# joint_board_boosterpack_load_cell.net
KiCad netlist of a schematic drawn in Altium Designer
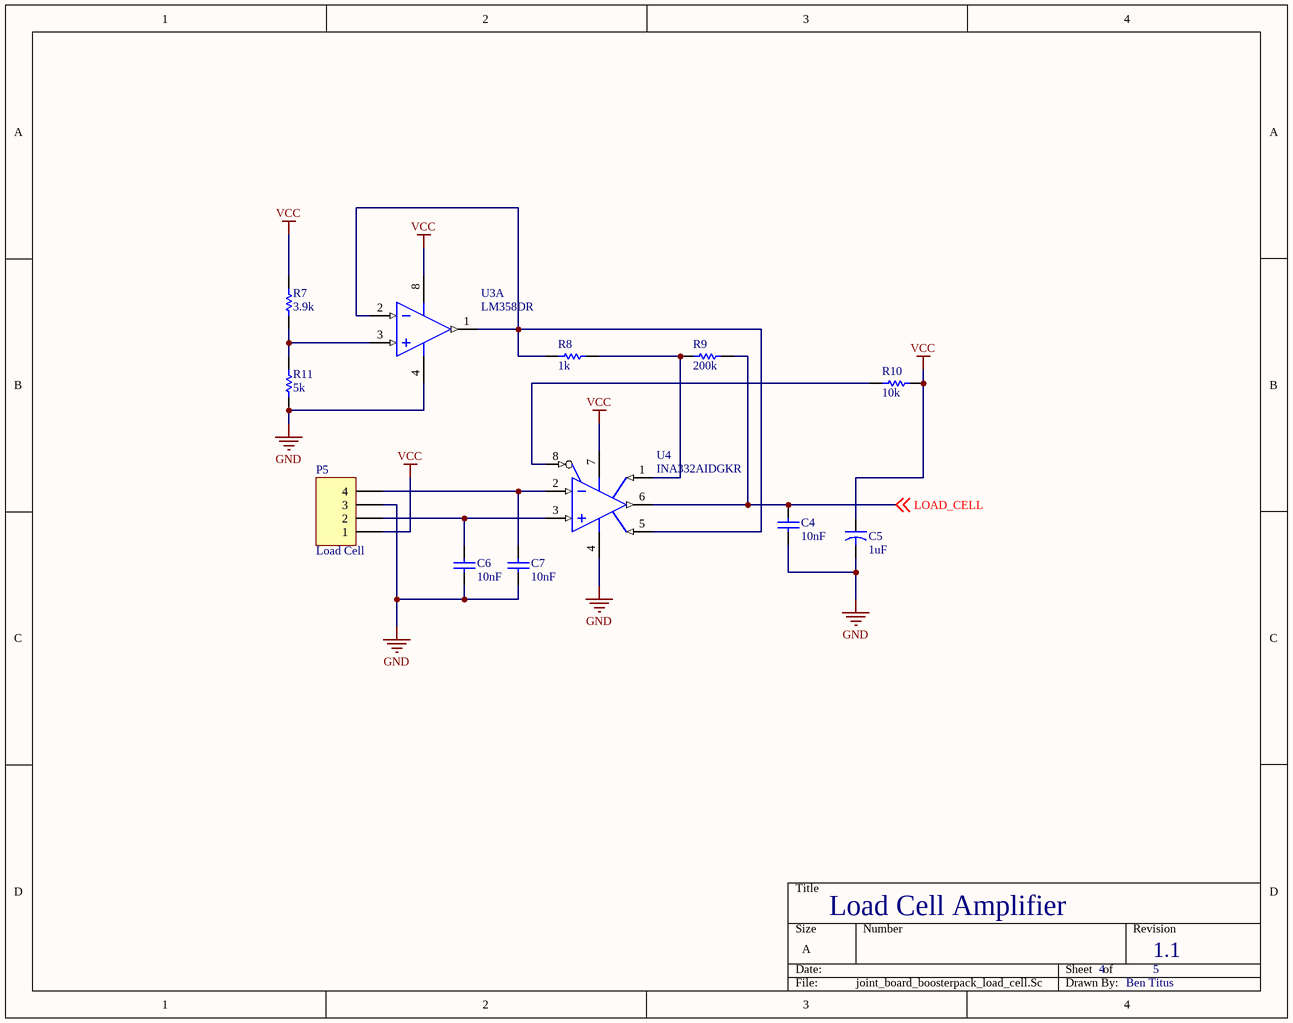
[diagram p0: joint_board_boosterpack_load_cell.SchDoc]

(export (version "E")
  (design (tool "Eeschema 10.0.6"))
  (components
    (comp (ref "C4")
      (value "10nF")
      (footprint "CAPC0805(2012)145_L")
      (description "0805 (2012 Metric) Chip Capacitor")
      (libsource (lib "Altium Content Vault") (part "CAP_5"))
    )
    (comp (ref "C5")
      (value "1uF")
      (footprint "CAPR5-4X5")
      (description "Capacitor")
      (fields (field (name "PUBLISHER") "Altium Limited"))
      (libsource (lib "Miscellaneous Devices") (part "Cap2"))
    )
    (comp (ref "C6")
      (value "10nF")
      (footprint "CAPC0805(2012)145_L")
      (description "0805 (2012 Metric) Chip Capacitor")
      (libsource (lib "Altium Content Vault") (part "CAP_5"))
    )
    (comp (ref "C7")
      (value "10nF")
      (footprint "CAPC0805(2012)145_L")
      (description "0805 (2012 Metric) Chip Capacitor")
      (libsource (lib "Altium Content Vault") (part "CAP_5"))
    )
    (comp (ref "P5")
      (value "Load Cell")
      (footprint "HDR1X4")
      (description "Header, 4-Pin")
      (fields (field (name "PUBLISHER") "Altium Limited"))
      (libsource (lib "Miscellaneous Connectors") (part "Header 4"))
    )
    (comp (ref "R7")
      (value "3.9k")
      (footprint "RESC0805(2012)_L")
      (description "0805 (2012 Metric) Chip Resistor")
      (libsource (lib "Altium Content Vault") (part "RES_3"))
    )
    (comp (ref "R8")
      (value "1k")
      (footprint "RESC0805(2012)_L")
      (description "0805 (2012 Metric) Chip Resistor")
      (libsource (lib "Altium Content Vault") (part "RES_3"))
    )
    (comp (ref "R9")
      (value "200k")
      (footprint "RESC0805(2012)_L")
      (description "0805 (2012 Metric) Chip Resistor")
      (libsource (lib "Altium Content Vault") (part "RES_3"))
    )
    (comp (ref "R10")
      (value "10k")
      (footprint "RESC0805(2012)_L")
      (description "0805 (2012 Metric) Chip Resistor")
      (libsource (lib "Altium Content Vault") (part "RES_3"))
    )
    (comp (ref "R11")
      (value "5k")
      (footprint "RESC0805(2012)_L")
      (description "0805 (2012 Metric) Chip Resistor")
      (libsource (lib "Altium Content Vault") (part "RES_3"))
    )
    (comp (ref "U3")
      (value "LM358DR")
      (footprint "D0008A_L")
      (libsource (lib "Altium Content Vault") (part "TI-LM358-8"))
    )
    (comp (ref "U4")
      (value "INA332AIDGKR")
      (footprint "DGK0008A_M")
      (fields (field (name "MANUFACTURER") "Texas Instruments"))
      (libsource (lib "Custom_Lib") (part "CMP-0944-00077-2"))
    )
  )
  (nets
    (net (code "1") (name "GND") (class "Default")
      (node (ref "C4") (pin "1") (pinfunction "1_1") (pintype "passive"))
      (node (ref "C5") (pin "2") (pinfunction "2_2") (pintype "passive"))
      (node (ref "C6") (pin "1") (pinfunction "1_1") (pintype "passive"))
      (node (ref "C7") (pin "1") (pinfunction "1_1") (pintype "passive"))
      (node (ref "P5") (pin "3") (pinfunction "3_3") (pintype "passive"))
      (node (ref "R11") (pin "1") (pinfunction "1_1") (pintype "passive"))
      (node (ref "U3") (pin "4") (pinfunction "GND_4") (pintype "power_in"))
      (node (ref "U4") (pin "4") (pinfunction "V-_4") (pintype "power_in"))
    )
    (net (code "2") (name "LOAD_CELL") (class "Default")
      (node (ref "C4") (pin "2") (pinfunction "2_2") (pintype "passive"))
      (node (ref "R9") (pin "2") (pinfunction "2_2") (pintype "passive"))
      (node (ref "U4") (pin "6") (pinfunction "VOUT_6") (pintype "output"))
    )
    (net (code "3") (name "Net-(U3A-1IN+)") (class "Default")
      (node (ref "R11") (pin "2") (pinfunction "2_2") (pintype "passive"))
      (node (ref "R7") (pin "1") (pinfunction "1_1") (pintype "passive"))
      (node (ref "U3") (pin "3") (pinfunction "1IN+_3") (pintype "input"))
    )
    (net (code "4") (name "Net-(U3A-1IN-)") (class "Default")
      (node (ref "R8") (pin "1") (pinfunction "1_1") (pintype "passive"))
      (node (ref "U3") (pin "1") (pinfunction "1OUT_1") (pintype "output"))
      (node (ref "U3") (pin "2") (pinfunction "1IN-_2") (pintype "input"))
      (node (ref "U4") (pin "5") (pinfunction "REF_5") (pintype "input"))
    )
    (net (code "5") (name "Net-(U4-RG)") (class "Default")
      (node (ref "R8") (pin "2") (pinfunction "2_2") (pintype "passive"))
      (node (ref "R9") (pin "1") (pinfunction "1_1") (pintype "passive"))
      (node (ref "U4") (pin "1") (pinfunction "RG_1") (pintype "input"))
    )
    (net (code "6") (name "Net-(U4-SHUTDOWN)") (class "Default")
      (node (ref "R10") (pin "2") (pinfunction "2_2") (pintype "passive"))
      (node (ref "U4") (pin "8") (pinfunction "SHUTDOWN_8") (pintype "input"))
    )
    (net (code "7") (name "Net-(U4-VIN+)") (class "Default")
      (node (ref "C6") (pin "2") (pinfunction "2_2") (pintype "passive"))
      (node (ref "P5") (pin "2") (pinfunction "2_2") (pintype "passive"))
      (node (ref "U4") (pin "3") (pinfunction "VIN+_3") (pintype "input"))
    )
    (net (code "8") (name "Net-(U4-VIN-)") (class "Default")
      (node (ref "C7") (pin "2") (pinfunction "2_2") (pintype "passive"))
      (node (ref "P5") (pin "4") (pinfunction "4_4") (pintype "passive"))
      (node (ref "U4") (pin "2") (pinfunction "VIN-_2") (pintype "input"))
    )
    (net (code "9") (name "VCC") (class "Default")
      (node (ref "C5") (pin "1") (pinfunction "1_1") (pintype "passive"))
      (node (ref "P5") (pin "1") (pinfunction "1_1") (pintype "passive"))
      (node (ref "R10") (pin "1") (pinfunction "1_1") (pintype "passive"))
      (node (ref "R7") (pin "2") (pinfunction "2_2") (pintype "passive"))
      (node (ref "U3") (pin "8") (pinfunction "VCC_8") (pintype "power_in"))
      (node (ref "U4") (pin "7") (pinfunction "V+_7") (pintype "power_in"))
    )
  )
)
